# RAM.net
KiCad netlist of a schematic drawn in Altium Designer
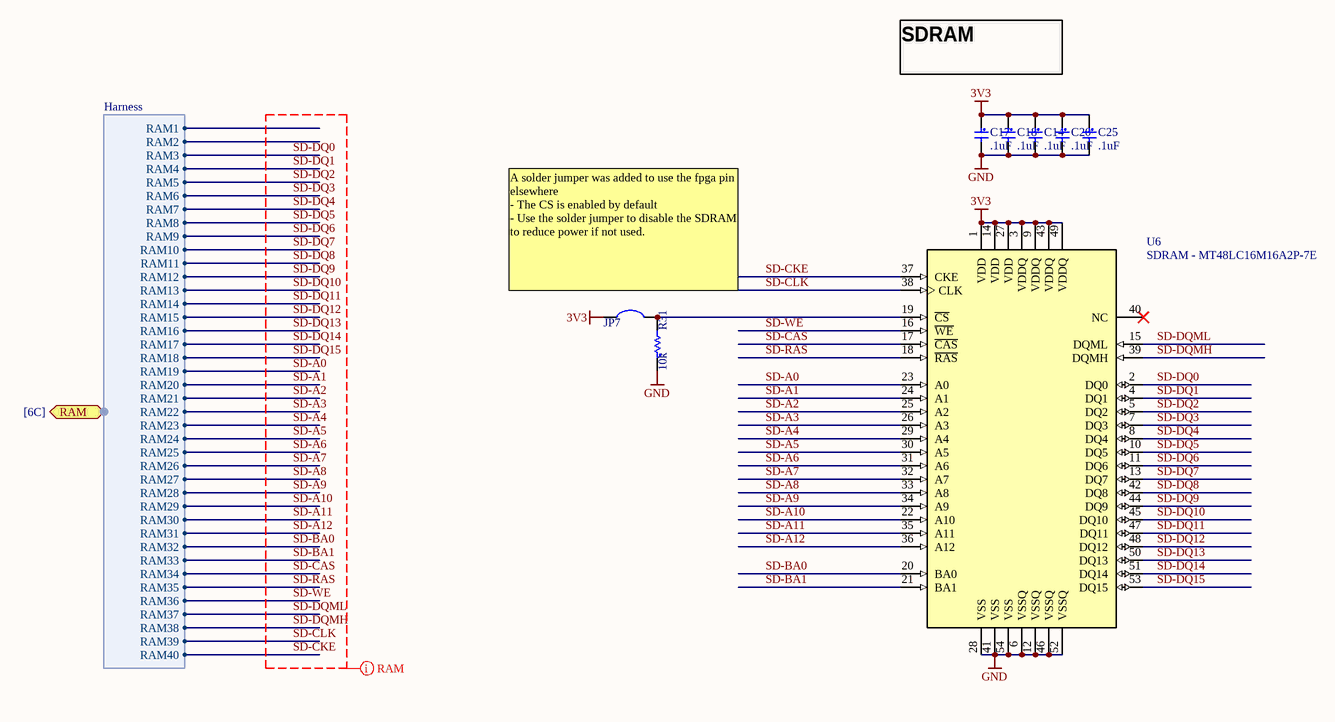
[diagram p0: RAM.SchDoc]

(export (version "E")
  (design (tool "Eeschema 10.0.6"))
  (components
    (comp (ref "C14")
      (value ".1uF")
      (footprint "c0603")
      (description "CAP CER 0.1UF 25V Y5V 0603")
      (fields
        (field (name "MANUFACTURER") "Samsung Electro-Mechanics America, Inc")
        (field (name "MANUFACTURER PART NUMBER") "CL10F104ZA8NNNC")
      )
      (libsource (lib "mCapacitors") (part "C0603 - CL10F104ZA8NNNC"))
    )
    (comp (ref "C17")
      (value ".1uF")
      (footprint "c0603")
      (description "CAP CER 0.1UF 25V Y5V 0603")
      (fields
        (field (name "MANUFACTURER") "Samsung Electro-Mechanics America, Inc")
        (field (name "MANUFACTURER PART NUMBER") "CL10F104ZA8NNNC")
      )
      (libsource (lib "mCapacitors") (part "C0603 - CL10F104ZA8NNNC"))
    )
    (comp (ref "C18")
      (value ".1uF")
      (footprint "c0603")
      (description "CAP CER 0.1UF 25V Y5V 0603")
      (fields
        (field (name "MANUFACTURER") "Samsung Electro-Mechanics America, Inc")
        (field (name "MANUFACTURER PART NUMBER") "CL10F104ZA8NNNC")
      )
      (libsource (lib "mCapacitors") (part "C0603 - CL10F104ZA8NNNC"))
    )
    (comp (ref "C20")
      (value ".1uF")
      (footprint "c0603")
      (description "CAP CER 0.1UF 25V Y5V 0603")
      (fields
        (field (name "MANUFACTURER") "Samsung Electro-Mechanics America, Inc")
        (field (name "MANUFACTURER PART NUMBER") "CL10F104ZA8NNNC")
      )
      (libsource (lib "mCapacitors") (part "C0603 - CL10F104ZA8NNNC"))
    )
    (comp (ref "C25")
      (value ".1uF")
      (footprint "c0603")
      (description "CAP CER 0.1UF 25V Y5V 0603")
      (fields
        (field (name "MANUFACTURER") "Samsung Electro-Mechanics America, Inc")
        (field (name "MANUFACTURER PART NUMBER") "CL10F104ZA8NNNC")
      )
      (libsource (lib "mCapacitors") (part "C0603 - CL10F104ZA8NNNC"))
    )
    (comp (ref "JP7")
      (value "Solder Jumper")
      (footprint "SOLDER_JUMPER")
      (description "Solder/Configuration Jumper")
      (fields (field (name "MANUFACTURER") "n/a"))
      (libsource (lib "mConnector") (part "Solder Jumper"))
    )
    (comp (ref "R31")
      (value "10k")
      (footprint "mRCL:R0603")
      (description "10k Thick Film Resistors - SMD 1/10watt 10Kohms 1%")
      (fields
        (field (name "MANUFACTURER") "Vishay Dale")
        (field (name "MANUFACTURER PART NUMBER") "CRCW060310K0FKEA")
      )
      (libsource (lib "mResistors") (part "R0603 - CRCW060310K0FKEA"))
    )
    (comp (ref "U6")
      (value "SDRAM - MT48LC16M16A2P-7E")
      (footprint "mic:TSOP2-54_L")
      (description "256Mb Synchronous High-Speed CMOS DRAM, 16Mb x 16Bit x 4 Banks, 54-Pin TSOP Pb-free, Commercial")
      (fields
        (field (name "MANUFACTURER") "MICRON")
        (field (name "MANUFACTURER PART NUMBER") "MT48LC16M16A2P-7E IT:G")
      )
      (libsource (lib "mIC") (part "SDRAM - MT48LC16M16A2P-7E"))
    )
  )
  (nets
    (net (code "2") (name "/SD-A0") (class "Default")
      (node (ref "U6") (pin "23") (pinfunction "A0_23") (pintype "input"))
    )
    (net (code "3") (name "/SD-A1") (class "Default")
      (node (ref "U6") (pin "24") (pinfunction "A1_24") (pintype "input"))
    )
    (net (code "4") (name "/SD-A2") (class "Default")
      (node (ref "U6") (pin "25") (pinfunction "A2_25") (pintype "input"))
    )
    (net (code "5") (name "/SD-A3") (class "Default")
      (node (ref "U6") (pin "26") (pinfunction "A3_26") (pintype "input"))
    )
    (net (code "6") (name "/SD-A4") (class "Default")
      (node (ref "U6") (pin "29") (pinfunction "A4_29") (pintype "input"))
    )
    (net (code "7") (name "/SD-A5") (class "Default")
      (node (ref "U6") (pin "30") (pinfunction "A5_30") (pintype "input"))
    )
    (net (code "8") (name "/SD-A6") (class "Default")
      (node (ref "U6") (pin "31") (pinfunction "A6_31") (pintype "input"))
    )
    (net (code "9") (name "/SD-A7") (class "Default")
      (node (ref "U6") (pin "32") (pinfunction "A7_32") (pintype "input"))
    )
    (net (code "10") (name "/SD-A8") (class "Default")
      (node (ref "U6") (pin "33") (pinfunction "A8_33") (pintype "input"))
    )
    (net (code "11") (name "/SD-A9") (class "Default")
      (node (ref "U6") (pin "34") (pinfunction "A9_34") (pintype "input"))
    )
    (net (code "12") (name "/SD-A10") (class "Default")
      (node (ref "U6") (pin "22") (pinfunction "A10_22") (pintype "input"))
    )
    (net (code "13") (name "/SD-A11") (class "Default")
      (node (ref "U6") (pin "35") (pinfunction "A11_35") (pintype "input"))
    )
    (net (code "14") (name "/SD-A12") (class "Default")
      (node (ref "U6") (pin "36") (pinfunction "A12_36") (pintype "input"))
    )
    (net (code "15") (name "/SD-BA0") (class "Default")
      (node (ref "U6") (pin "20") (pinfunction "BA0_20") (pintype "input"))
    )
    (net (code "16") (name "/SD-BA1") (class "Default")
      (node (ref "U6") (pin "21") (pinfunction "BA1_21") (pintype "input"))
    )
    (net (code "17") (name "/SD-CAS") (class "Default")
      (node (ref "U6") (pin "17") (pinfunction "~{CAS}_17") (pintype "input"))
    )
    (net (code "18") (name "/SD-CKE") (class "Default")
      (node (ref "U6") (pin "37") (pinfunction "CKE_37") (pintype "input"))
    )
    (net (code "19") (name "/SD-CLK") (class "Default")
      (node (ref "U6") (pin "38") (pinfunction "CLK_38") (pintype "input"))
    )
    (net (code "20") (name "/SD-DQ0") (class "Default")
      (node (ref "U6") (pin "2") (pinfunction "DQ0_2") (pintype "bidirectional"))
    )
    (net (code "21") (name "/SD-DQ1") (class "Default")
      (node (ref "U6") (pin "4") (pinfunction "DQ1_4") (pintype "bidirectional"))
    )
    (net (code "22") (name "/SD-DQ2") (class "Default")
      (node (ref "U6") (pin "5") (pinfunction "DQ2_5") (pintype "bidirectional"))
    )
    (net (code "23") (name "/SD-DQ3") (class "Default")
      (node (ref "U6") (pin "7") (pinfunction "DQ3_7") (pintype "bidirectional"))
    )
    (net (code "24") (name "/SD-DQ4") (class "Default")
      (node (ref "U6") (pin "8") (pinfunction "DQ4_8") (pintype "bidirectional"))
    )
    (net (code "25") (name "/SD-DQ5") (class "Default")
      (node (ref "U6") (pin "10") (pinfunction "DQ5_10") (pintype "bidirectional"))
    )
    (net (code "26") (name "/SD-DQ6") (class "Default")
      (node (ref "U6") (pin "11") (pinfunction "DQ6_11") (pintype "bidirectional"))
    )
    (net (code "27") (name "/SD-DQ7") (class "Default")
      (node (ref "U6") (pin "13") (pinfunction "DQ7_13") (pintype "bidirectional"))
    )
    (net (code "28") (name "/SD-DQ8") (class "Default")
      (node (ref "U6") (pin "42") (pinfunction "DQ8_42") (pintype "bidirectional"))
    )
    (net (code "29") (name "/SD-DQ9") (class "Default")
      (node (ref "U6") (pin "44") (pinfunction "DQ9_44") (pintype "bidirectional"))
    )
    (net (code "30") (name "/SD-DQ10") (class "Default")
      (node (ref "U6") (pin "45") (pinfunction "DQ10_45") (pintype "bidirectional"))
    )
    (net (code "31") (name "/SD-DQ11") (class "Default")
      (node (ref "U6") (pin "47") (pinfunction "DQ11_47") (pintype "bidirectional"))
    )
    (net (code "32") (name "/SD-DQ12") (class "Default")
      (node (ref "U6") (pin "48") (pinfunction "DQ12_48") (pintype "bidirectional"))
    )
    (net (code "33") (name "/SD-DQ13") (class "Default")
      (node (ref "U6") (pin "50") (pinfunction "DQ13_50") (pintype "bidirectional"))
    )
    (net (code "34") (name "/SD-DQ14") (class "Default")
      (node (ref "U6") (pin "51") (pinfunction "DQ14_51") (pintype "bidirectional"))
    )
    (net (code "35") (name "/SD-DQ15") (class "Default")
      (node (ref "U6") (pin "53") (pinfunction "DQ15_53") (pintype "bidirectional"))
    )
    (net (code "36") (name "/SD-DQMH") (class "Default")
      (node (ref "U6") (pin "39") (pinfunction "DQMH_39") (pintype "input"))
    )
    (net (code "37") (name "/SD-DQML") (class "Default")
      (node (ref "U6") (pin "15") (pinfunction "DQML_15") (pintype "input"))
    )
    (net (code "38") (name "/SD-RAS") (class "Default")
      (node (ref "U6") (pin "18") (pinfunction "~{RAS}_18") (pintype "input"))
    )
    (net (code "39") (name "/SD-WE") (class "Default")
      (node (ref "U6") (pin "16") (pinfunction "~{WE}_16") (pintype "input"))
    )
    (net (code "41") (name "3V3") (class "Default")
      (node (ref "C14") (pin "1") (pinfunction "1_1") (pintype "passive"))
      (node (ref "C17") (pin "1") (pinfunction "1_1") (pintype "passive"))
      (node (ref "C18") (pin "1") (pinfunction "1_1") (pintype "passive"))
      (node (ref "C20") (pin "1") (pinfunction "1_1") (pintype "passive"))
      (node (ref "C25") (pin "1") (pinfunction "1_1") (pintype "passive"))
      (node (ref "JP7") (pin "1") (pinfunction "1_1") (pintype "passive"))
      (node (ref "U6") (pin "1") (pinfunction "VDD_1") (pintype "power_in"))
      (node (ref "U6") (pin "14") (pinfunction "VDD_14") (pintype "power_in"))
      (node (ref "U6") (pin "27") (pinfunction "VDD_27") (pintype "power_in"))
      (node (ref "U6") (pin "3") (pinfunction "VDDQ_3") (pintype "power_in"))
      (node (ref "U6") (pin "43") (pinfunction "VDDQ_43") (pintype "power_in"))
      (node (ref "U6") (pin "49") (pinfunction "VDDQ_49") (pintype "power_in"))
      (node (ref "U6") (pin "9") (pinfunction "VDDQ_9") (pintype "power_in"))
    )
    (net (code "42") (name "GND") (class "Default")
      (node (ref "C14") (pin "2") (pinfunction "2_2") (pintype "passive"))
      (node (ref "C17") (pin "2") (pinfunction "2_2") (pintype "passive"))
      (node (ref "C18") (pin "2") (pinfunction "2_2") (pintype "passive"))
      (node (ref "C20") (pin "2") (pinfunction "2_2") (pintype "passive"))
      (node (ref "C25") (pin "2") (pinfunction "2_2") (pintype "passive"))
      (node (ref "R31") (pin "1") (pinfunction "1_1") (pintype "passive"))
      (node (ref "U6") (pin "12") (pinfunction "VSSQ_12") (pintype "power_in"))
      (node (ref "U6") (pin "28") (pinfunction "VSS_28") (pintype "power_in"))
      (node (ref "U6") (pin "41") (pinfunction "VSS_41") (pintype "power_in"))
      (node (ref "U6") (pin "46") (pinfunction "VSSQ_46") (pintype "power_in"))
      (node (ref "U6") (pin "52") (pinfunction "VSSQ_52") (pintype "power_in"))
      (node (ref "U6") (pin "54") (pinfunction "VSS_54") (pintype "power_in"))
      (node (ref "U6") (pin "6") (pinfunction "VSSQ_6") (pintype "power_in"))
    )
    (net (code "43") (name "Net-(U6-~{CS})") (class "Default")
      (node (ref "JP7") (pin "2") (pinfunction "2_2") (pintype "passive"))
      (node (ref "R31") (pin "2") (pinfunction "2_2") (pintype "passive"))
      (node (ref "U6") (pin "19") (pinfunction "~{CS}_19") (pintype "input"))
    )
    (net (code "44") (name "unconnected-(U6-NC-Pad40)") (class "Default")
      (node (ref "U6") (pin "40") (pinfunction "NC_40") (pintype "passive+no_connect"))
    )
  )
)
